# DE-130624.net
KiCad netlist of a schematic drawn in Altium Designer
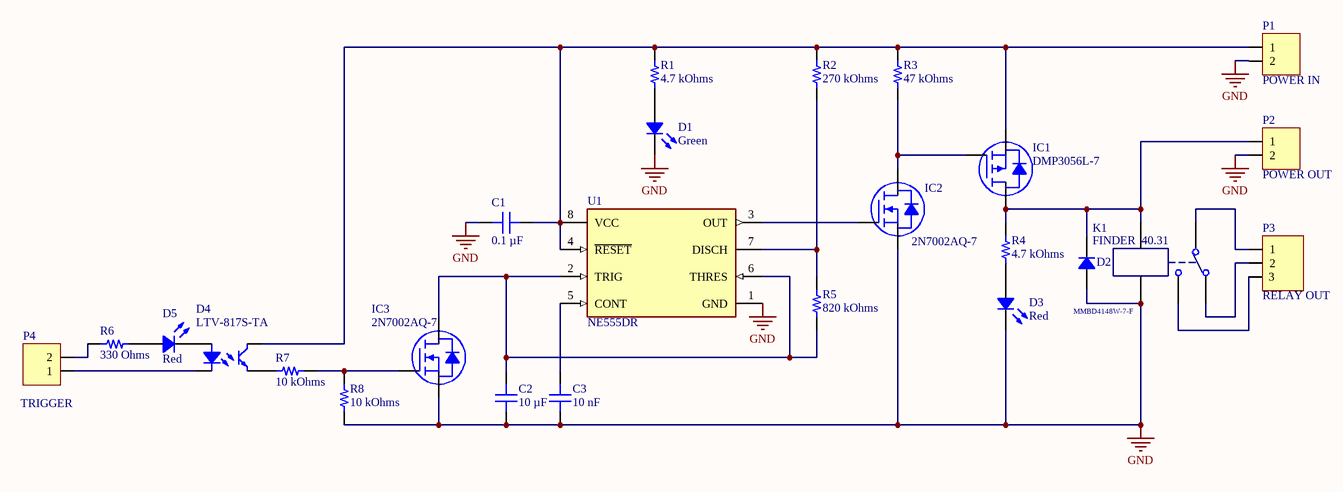
[diagram p0: DE-130624.SchDoc]

(export (version "E")
  (design (tool "Eeschema 10.0.6"))
  (components
    (comp (ref "C1")
      (value "0.1 µF")
      (footprint "CAP 0603_1608")
      (description "CAP CER 0.1UF 50V X7R 0603")
      (fields (field (name "PART NUMBER") "C0603C104K5RAC7411") (field (name "MANUFACTURER") "KEMET"))
      (libsource (lib "Celestial Altium Library - altium_library") (part "Capacitor"))
    )
    (comp (ref "C2")
      (value "10 µF")
      (footprint "CAP 0805_2012")
      (description "CAP CER 10UF 35V X5R 0805")
      (fields (field (name "PART NUMBER") "GMK212BBJ106KG-T") (field (name "MANUFACTURER") "Taiyo Yuden"))
      (libsource (lib "Celestial Altium Library - altium_library") (part "Capacitor"))
    )
    (comp (ref "C3")
      (value "10 nF")
      (footprint "CAP 0603_1608")
      (description "CAP CER 0603 10NF 100V X7R")
      (fields (field (name "PART NUMBER") "C0603X103K1RAC3316") (field (name "MANUFACTURER") "KEMET"))
      (libsource (lib "Celestial Altium Library - altium_library") (part "Capacitor"))
    )
    (comp (ref "D1")
      (value "Green")
      (footprint "DE-220817:1.6X0.8X0.8")
      (description "LED GREEN CLEAR SMD")
      (fields (field (name "PART NUMBER") "LTST-C170KGKT") (field (name "MANUFACTURER") "Lite-On Inc."))
      (libsource (lib "Celestial Altium Library - altium_library") (part "LED"))
    )
    (comp (ref "D2")
      (value "MMBD4148W-7-F")
      (footprint "DIODES SOT-323-3")
      (description "DIODE GEN PURP 75V 150MA SOT323")
      (fields (field (name "MANUFACTURER") "Diodes Incorporated"))
      (libsource (lib "Celestial Altium Library - altium_library") (part "Diode"))
    )
    (comp (ref "D3")
      (value "Red")
      (footprint "DE-220817:1.6X0.8X0.8")
      (description "LED RED CLEAR SMD")
      (fields (field (name "PART NUMBER") "LTST-C170KAKT") (field (name "MANUFACTURER") "Lite-On Inc."))
      (libsource (lib "Celestial Altium Library - altium_library") (part "LED"))
    )
    (comp (ref "D4")
      (value "LTV-817S-TA")
      (footprint "LITEON LTV-817")
      (description "OPTOISOLATR 5KV TRANSISTOR 4-SMD")
      (fields (field (name "MANUFACTURER") "Lite-On Inc."))
      (libsource (lib "Celestial Altium Library - altium_library") (part "Optoisolator"))
    )
    (comp (ref "D5")
      (value "Red")
      (footprint "DE-220817:1.6X0.8X0.8")
      (description "LED RED CLEAR SMD")
      (fields (field (name "PART NUMBER") "LTST-C170KAKT") (field (name "MANUFACTURER") "Lite-On Inc."))
      (libsource (lib "Celestial Altium Library - altium_library") (part "LED"))
    )
    (comp (ref "IC1")
      (value "DMP3056L-7")
      (footprint "DIODES SOT-23-3")
      (description "MOSFET P-CH 30V 4.3A SOT23")
      (fields (field (name "MANUFACTURER") "Diodes Incorporated"))
      (libsource (lib "Celestial Altium Library - altium_library") (part "DIODES MOSFET P-CH SOT-23-3"))
    )
    (comp (ref "IC2")
      (value "2N7002AQ-7")
      (footprint "DIODES SOT-23-3")
      (description "MOSFET N-CH 60V 180MA SOT23")
      (fields (field (name "MANUFACTURER") "Diodes Incorporated"))
      (libsource (lib "Celestial Altium Library - altium_library") (part "DIODES INC MOSFET N-CH SOT-23-3"))
    )
    (comp (ref "IC3")
      (value "2N7002AQ-7")
      (footprint "DIODES SOT-23-3")
      (description "MOSFET N-CH 60V 180MA SOT23")
      (fields (field (name "MANUFACTURER") "Diodes Incorporated"))
      (libsource (lib "Celestial Altium Library - altium_library") (part "DIODES INC MOSFET N-CH SOT-23-3"))
    )
    (comp (ref "K1")
      (value "FINDER  40.31")
      (footprint "FINDER 40.31")
      (libsource (lib "DE-220817") (part "FINDER RELAY 40.31"))
    )
    (comp (ref "P1")
      (value "POWER IN")
      (footprint "TERMINAL BLOK 2")
      (description "Terminal blok konektor 3,5 mm")
      (libsource (lib "DE-220817") (part "TERMINAL BLOK 2"))
    )
    (comp (ref "P2")
      (value "POWER OUT")
      (footprint "TERMINAL BLOK 2")
      (description "Terminal blok konektor 3,5 mm")
      (libsource (lib "") (part "TERMINAL BLOK 2_2"))
    )
    (comp (ref "P3")
      (value "RELAY OUT")
      (footprint "TERMINAL BLOK 3")
      (description "3 pinski terminal blok konektor")
      (libsource (lib "DE-220817") (part "TERMINAL BLOK 3"))
    )
    (comp (ref "P4")
      (value "TRIGGER")
      (footprint "TERMINAL BLOK 2")
      (description "Terminal blok konektor 3,5 mm")
      (libsource (lib "") (part "TERMINAL BLOK 2_1"))
    )
    (comp (ref "R1")
      (value "4.7 kOhms")
      (footprint "RES 0805_2012")
      (description "RES 4.7K OHM 1% 1/4W 0805")
      (fields (field (name "PART NUMBER") "AC0805FR-7W4K7L") (field (name "MANUFACTURER") "Yageo"))
      (libsource (lib "Celestial Altium Library - altium_library") (part "Resistor"))
    )
    (comp (ref "R2")
      (value "270 kOhms")
      (footprint "RES 0805_2012")
      (description "RES SMD 270K OHM 1% 1/8W 0805")
      (fields (field (name "PART NUMBER") "AC0805FR-07270KL") (field (name "MANUFACTURER") "Yageo"))
      (libsource (lib "Celestial Altium Library - altium_library") (part "Resistor"))
    )
    (comp (ref "R3")
      (value "47 kOhms")
      (footprint "RES 0805_2012")
      (description "RES SMD 47K OHM 1% 1/8W 0805")
      (fields (field (name "PART NUMBER") "AC0805FR-0747KL") (field (name "MANUFACTURER") "Yageo"))
      (libsource (lib "Celestial Altium Library - altium_library") (part "Resistor"))
    )
    (comp (ref "R4")
      (value "4.7 kOhms")
      (footprint "RES 0805_2012")
      (description "RES 4.7K OHM 1% 1/4W 0805")
      (fields (field (name "PART NUMBER") "AC0805FR-7W4K7L") (field (name "MANUFACTURER") "Yageo"))
      (libsource (lib "Celestial Altium Library - altium_library") (part "Resistor"))
    )
    (comp (ref "R5")
      (value "820 kOhms")
      (footprint "RES 0805_2012")
      (description "RES SMD 820K OHM 1% 1/8W 0805")
      (fields (field (name "PART NUMBER") "AC0805FR-07820KL") (field (name "MANUFACTURER") "Yageo"))
      (libsource (lib "Celestial Altium Library - altium_library") (part "Resistor"))
    )
    (comp (ref "R6")
      (value "330 Ohms")
      (footprint "RES 0805_2012")
      (description "RES 1K OHM 1% 1/8W 0805")
      (fields (field (name "PART NUMBER") "AT0805FRE071KL") (field (name "MANUFACTURER") "Yageo"))
      (libsource (lib "Celestial Altium Library - altium_library") (part "Resistor"))
    )
    (comp (ref "R7")
      (value "10 kOhms")
      (footprint "RES 0805_2012")
      (description "RES SMD 10K OHM 1% 1/8W 0805")
      (fields (field (name "PART NUMBER") "AA0805FR-0710KL") (field (name "MANUFACTURER") "Yageo"))
      (libsource (lib "Celestial Altium Library - altium_library") (part "Resistor"))
    )
    (comp (ref "R8")
      (value "10 kOhms")
      (footprint "RES 0805_2012")
      (description "RES SMD 27K OHM 1% 1/8W 0805")
      (fields (field (name "PART NUMBER") "AC0805FR-0727KL") (field (name "MANUFACTURER") "Yageo"))
      (libsource (lib "Celestial Altium Library - altium_library") (part "Resistor"))
    )
    (comp (ref "U1")
      (value "NE555DR")
      (footprint "FP-D0008A-IPC_B")
      (description "IC OSC SGL TIMER 100KHZ 8-SOIC")
      (libsource (lib "Components - 13.06.24 - 15.35") (part "CMP-1685-00007-2"))
    )
  )
  (nets
    (net (code "1") (name "GND") (class "Default")
      (node (ref "C1") (pin "1") (pinfunction "1_1") (pintype "passive"))
      (node (ref "C2") (pin "1") (pinfunction "1_1") (pintype "passive"))
      (node (ref "C3") (pin "1") (pinfunction "1_1") (pintype "passive"))
      (node (ref "D1") (pin "2") (pinfunction "2_2") (pintype "passive"))
      (node (ref "D2") (pin "1") (pinfunction "1_1") (pintype "passive"))
      (node (ref "D3") (pin "2") (pinfunction "2_2") (pintype "passive"))
      (node (ref "IC2") (pin "2") (pinfunction "S_2") (pintype "passive"))
      (node (ref "IC3") (pin "2") (pinfunction "S_2") (pintype "passive"))
      (node (ref "K1") (pin "2") (pinfunction "2_2") (pintype "passive"))
      (node (ref "P1") (pin "2") (pinfunction "2_2") (pintype "passive"))
      (node (ref "P2") (pin "2") (pinfunction "2_2") (pintype "passive"))
      (node (ref "R8") (pin "1") (pinfunction "1_1") (pintype "passive"))
      (node (ref "U1") (pin "1") (pinfunction "GND_1") (pintype "power_in"))
    )
    (net (code "2") (name "Net-(D1-Pad1)") (class "Default")
      (node (ref "D1") (pin "1") (pinfunction "1_1") (pintype "passive"))
      (node (ref "R1") (pin "1") (pinfunction "1_1") (pintype "passive"))
    )
    (net (code "3") (name "Net-(D3-Pad1)") (class "Default")
      (node (ref "D3") (pin "1") (pinfunction "1_1") (pintype "passive"))
      (node (ref "R4") (pin "1") (pinfunction "1_1") (pintype "passive"))
    )
    (net (code "4") (name "Net-(D4-Pad1)") (class "Default")
      (node (ref "D4") (pin "1") (pinfunction "1_1") (pintype "passive"))
      (node (ref "D5") (pin "2") (pinfunction "2_2") (pintype "passive"))
    )
    (net (code "5") (name "Net-(D4-Pad2)") (class "Default")
      (node (ref "D4") (pin "2") (pinfunction "2_2") (pintype "passive"))
      (node (ref "P4") (pin "1") (pinfunction "1_1") (pintype "passive"))
    )
    (net (code "6") (name "Net-(D4-Pad3)") (class "Default")
      (node (ref "D4") (pin "3") (pinfunction "3_3") (pintype "passive"))
      (node (ref "R7") (pin "2") (pinfunction "2_2") (pintype "passive"))
    )
    (net (code "7") (name "Net-(D5-Pad1)") (class "Default")
      (node (ref "D5") (pin "1") (pinfunction "1_1") (pintype "passive"))
      (node (ref "R6") (pin "2") (pinfunction "2_2") (pintype "passive"))
    )
    (net (code "8") (name "Net-(IC1-D)") (class "Default")
      (node (ref "D2") (pin "2") (pinfunction "2_2") (pintype "passive"))
      (node (ref "IC1") (pin "3") (pinfunction "D_3") (pintype "passive"))
      (node (ref "K1") (pin "1") (pinfunction "1_1") (pintype "passive"))
      (node (ref "P2") (pin "1") (pinfunction "1_1") (pintype "passive"))
      (node (ref "R4") (pin "2") (pinfunction "2_2") (pintype "passive"))
    )
    (net (code "9") (name "Net-(IC1-G)") (class "Default")
      (node (ref "IC1") (pin "1") (pinfunction "G_1") (pintype "passive"))
      (node (ref "IC2") (pin "3") (pinfunction "D_3") (pintype "passive"))
      (node (ref "R3") (pin "1") (pinfunction "1_1") (pintype "passive"))
    )
    (net (code "10") (name "Net-(IC1-S)") (class "Default")
      (node (ref "C1") (pin "2") (pinfunction "2_2") (pintype "passive"))
      (node (ref "D4") (pin "4") (pinfunction "4_4") (pintype "passive"))
      (node (ref "IC1") (pin "2") (pinfunction "S_2") (pintype "passive"))
      (node (ref "P1") (pin "1") (pinfunction "1_1") (pintype "passive"))
      (node (ref "R1") (pin "2") (pinfunction "2_2") (pintype "passive"))
      (node (ref "R2") (pin "2") (pinfunction "2_2") (pintype "passive"))
      (node (ref "R3") (pin "2") (pinfunction "2_2") (pintype "passive"))
      (node (ref "U1") (pin "4") (pinfunction "~{RESET}_4") (pintype "input"))
      (node (ref "U1") (pin "8") (pinfunction "VCC_8") (pintype "power_in"))
    )
    (net (code "11") (name "Net-(IC2-G)") (class "Default")
      (node (ref "IC2") (pin "1") (pinfunction "G_1") (pintype "passive"))
      (node (ref "U1") (pin "3") (pinfunction "OUT_3") (pintype "output"))
    )
    (net (code "12") (name "Net-(IC3-D)") (class "Default")
      (node (ref "C2") (pin "2") (pinfunction "2_2") (pintype "passive"))
      (node (ref "IC3") (pin "3") (pinfunction "D_3") (pintype "passive"))
      (node (ref "R5") (pin "1") (pinfunction "1_1") (pintype "passive"))
      (node (ref "U1") (pin "2") (pinfunction "TRIG_2") (pintype "input"))
      (node (ref "U1") (pin "6") (pinfunction "THRES_6") (pintype "input"))
    )
    (net (code "13") (name "Net-(IC3-G)") (class "Default")
      (node (ref "IC3") (pin "1") (pinfunction "G_1") (pintype "passive"))
      (node (ref "R7") (pin "1") (pinfunction "1_1") (pintype "passive"))
      (node (ref "R8") (pin "2") (pinfunction "2_2") (pintype "passive"))
    )
    (net (code "14") (name "Net-(K1-Pad3)") (class "Default")
      (node (ref "K1") (pin "3") (pinfunction "3_3") (pintype "passive"))
      (node (ref "P3") (pin "1") (pinfunction "1_1") (pintype "passive"))
    )
    (net (code "15") (name "Net-(K1-Pad4)") (class "Default")
      (node (ref "K1") (pin "4") (pinfunction "4_4") (pintype "passive"))
      (node (ref "P3") (pin "3") (pinfunction "3_3") (pintype "passive"))
    )
    (net (code "16") (name "Net-(K1-Pad5)") (class "Default")
      (node (ref "K1") (pin "5") (pinfunction "5_5") (pintype "passive"))
      (node (ref "P3") (pin "2") (pinfunction "2_2") (pintype "passive"))
    )
    (net (code "17") (name "Net-(P4-Pad2)") (class "Default")
      (node (ref "P4") (pin "2") (pinfunction "2_2") (pintype "passive"))
      (node (ref "R6") (pin "1") (pinfunction "1_1") (pintype "passive"))
    )
    (net (code "18") (name "Net-(U1-CONT)") (class "Default")
      (node (ref "C3") (pin "2") (pinfunction "2_2") (pintype "passive"))
      (node (ref "U1") (pin "5") (pinfunction "CONT_5") (pintype "input"))
    )
    (net (code "19") (name "Net-(U1-DISCH)") (class "Default")
      (node (ref "R2") (pin "1") (pinfunction "1_1") (pintype "passive"))
      (node (ref "R5") (pin "2") (pinfunction "2_2") (pintype "passive"))
      (node (ref "U1") (pin "7") (pinfunction "DISCH_7") (pintype "open_collector"))
    )
  )
)
